# LCR_1.net
KiCad netlist of a schematic drawn in Altium Designer
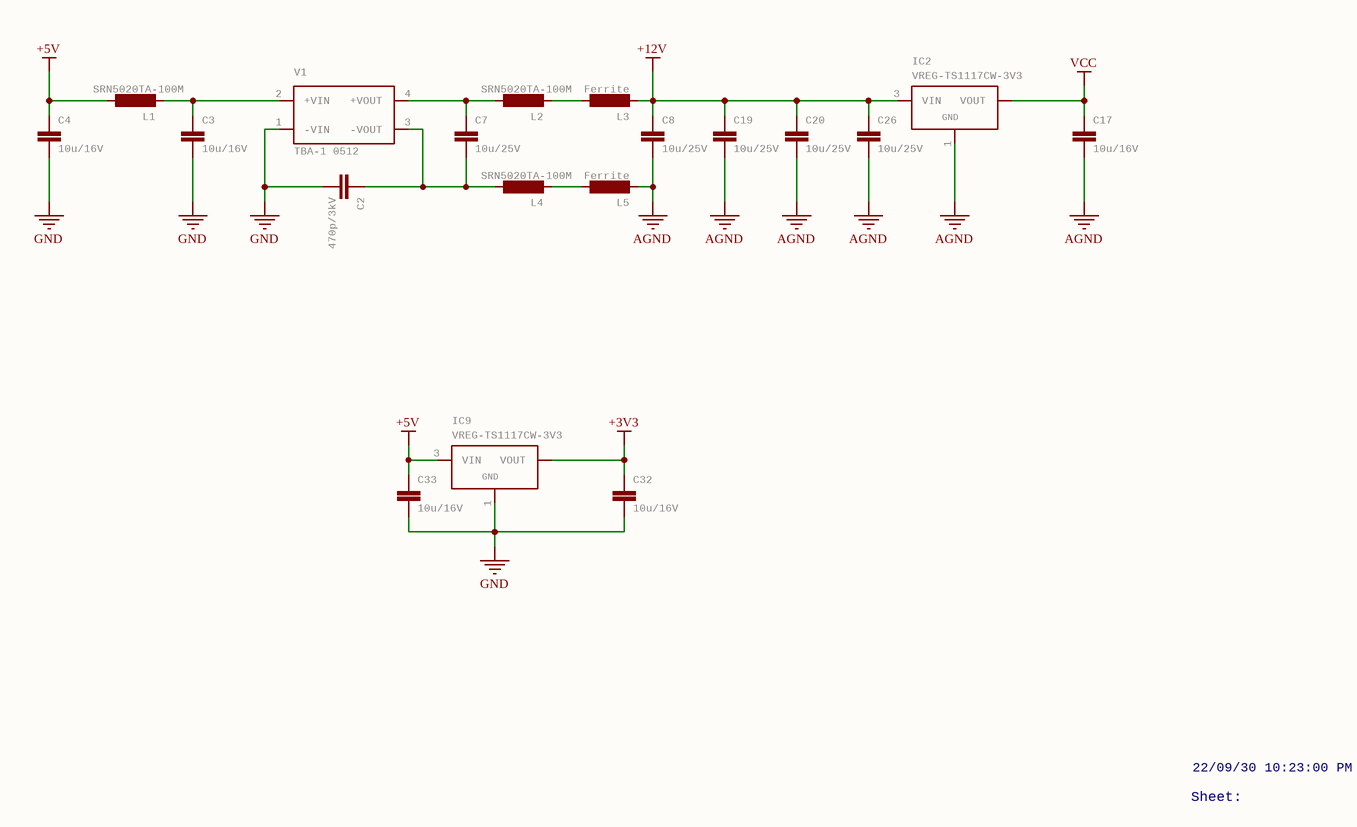
[diagram p0: LCR_1.SchDoc]

(export (version "E")
  (design (tool "Eeschema 10.0.6"))
  (components
    (comp (ref "C2")
      (value "470p/3kV")
      (footprint "C1812")
      (description "CAPACITOR, European symbol")
      (libsource (lib "resistor") (part "C-EUC1812"))
    )
    (comp (ref "C3")
      (value "10u/16V")
      (footprint "C1206K")
      (description "CAPACITOR, European symbol")
      (libsource (lib "rcl") (part "C-EUC1206K"))
    )
    (comp (ref "C4")
      (value "10u/16V")
      (footprint "C1206K")
      (description "CAPACITOR, European symbol")
      (libsource (lib "rcl") (part "C-EUC1206K"))
    )
    (comp (ref "C7")
      (value "10u/25V")
      (footprint "C1206K")
      (description "CAPACITOR, European symbol")
      (libsource (lib "rcl") (part "C-EUC1206K"))
    )
    (comp (ref "C8")
      (value "10u/25V")
      (footprint "C1206K")
      (description "CAPACITOR, European symbol")
      (libsource (lib "rcl") (part "C-EUC1206K"))
    )
    (comp (ref "C17")
      (value "10u/16V")
      (footprint "C1206K")
      (description "CAPACITOR, European symbol")
      (libsource (lib "rcl") (part "C-EUC1206K"))
    )
    (comp (ref "C19")
      (value "10u/25V")
      (footprint "C1206K")
      (description "CAPACITOR, European symbol")
      (libsource (lib "rcl") (part "C-EUC1206K"))
    )
    (comp (ref "C20")
      (value "10u/25V")
      (footprint "C1206K")
      (description "CAPACITOR, European symbol")
      (libsource (lib "rcl") (part "C-EUC1206K"))
    )
    (comp (ref "C26")
      (value "10u/25V")
      (footprint "C1206K")
      (description "CAPACITOR, European symbol")
      (libsource (lib "rcl") (part "C-EUC1206K"))
    )
    (comp (ref "C32")
      (value "10u/16V")
      (footprint "C1206K")
      (description "CAPACITOR, European symbol")
      (libsource (lib "rcl") (part "C-EUC1206K"))
    )
    (comp (ref "C33")
      (value "10u/16V")
      (footprint "C1206K")
      (description "CAPACITOR, European symbol")
      (libsource (lib "rcl") (part "C-EUC1206K"))
    )
    (comp (ref "IC2")
      (value "VREG-TS1117CW-3V3")
      (footprint "SOT223")
      (fields (field (name "GND") "GND"))
      (libsource (lib "we-power-mod") (part "VREG-TS1117CW-3V3"))
    )
    (comp (ref "IC9")
      (value "VREG-TS1117CW-3V3")
      (footprint "SOT223")
      (fields (field (name "GND") "GND"))
      (libsource (lib "we-power-mod") (part "VREG-TS1117CW-3V3"))
    )
    (comp (ref "L1")
      (value "SRN5020TA-100M")
      (footprint "SRN5040")
      (libsource (lib "custom-ic") (part "SRN5040"))
    )
    (comp (ref "L2")
      (value "SRN5020TA-100M")
      (footprint "SRN5040")
      (libsource (lib "custom-ic") (part "SRN5040"))
    )
    (comp (ref "L3") (value "Ferrite") (footprint "R0603") (libsource (lib "rf") (part "INDUCTOR0603")))
    (comp (ref "L4")
      (value "SRN5020TA-100M")
      (footprint "SRN5040")
      (libsource (lib "custom-ic") (part "SRN5040"))
    )
    (comp (ref "L5") (value "Ferrite") (footprint "R0603") (libsource (lib "rf") (part "INDUCTOR0603")))
    (comp (ref "V1")
      (value "TBA-1 0512")
      (footprint "TME")
      (description "DC/DC Converter TME Series 1 Watt    Source: www.tracopower.com .. tme.pdf")
      (fields (field (name "MF") "MF") (field (name "MPN") "TME 0505S"))
      (libsource (lib "traco-electronic") (part "TME?*05"))
    )
  )
  (nets
    (net (code "1") (name "+3V3") (class "Default")
      (node (ref "C32") (pin "1") (pinfunction "1_1") (pintype "passive"))
      (node (ref "IC9") (pin "2_4") (pinfunction "VOUT_2_4") (pintype "power_in"))
    )
    (net (code "2") (name "+5V") (class "Default")
      (node (ref "C33") (pin "1") (pinfunction "1_1") (pintype "passive"))
      (node (ref "C4") (pin "1") (pinfunction "1_1") (pintype "passive"))
      (node (ref "IC9") (pin "3") (pinfunction "VIN_3") (pintype "power_in"))
      (node (ref "L1") (pin "P$1") (pinfunction "1_P$1") (pintype "passive"))
    )
    (net (code "3") (name "+12V") (class "Default")
      (node (ref "C19") (pin "1") (pinfunction "1_1") (pintype "passive"))
      (node (ref "C20") (pin "1") (pinfunction "1_1") (pintype "passive"))
      (node (ref "C26") (pin "1") (pinfunction "1_1") (pintype "passive"))
      (node (ref "C8") (pin "1") (pinfunction "1_1") (pintype "passive"))
      (node (ref "IC2") (pin "3") (pinfunction "VIN_3") (pintype "power_in"))
      (node (ref "L3") (pin "2") (pinfunction "2_2") (pintype "passive"))
    )
    (net (code "4") (name "AGND") (class "Default")
      (node (ref "C17") (pin "2") (pinfunction "2_2") (pintype "passive"))
      (node (ref "C19") (pin "2") (pinfunction "2_2") (pintype "passive"))
      (node (ref "C20") (pin "2") (pinfunction "2_2") (pintype "passive"))
      (node (ref "C26") (pin "2") (pinfunction "2_2") (pintype "passive"))
      (node (ref "C8") (pin "2") (pinfunction "2_2") (pintype "passive"))
      (node (ref "IC2") (pin "1") (pinfunction "GND_1") (pintype "power_in"))
      (node (ref "L5") (pin "2") (pinfunction "2_2") (pintype "passive"))
    )
    (net (code "5") (name "GND") (class "Default")
      (node (ref "C2") (pin "2") (pinfunction "2_2") (pintype "passive"))
      (node (ref "C3") (pin "2") (pinfunction "2_2") (pintype "passive"))
      (node (ref "C32") (pin "2") (pinfunction "2_2") (pintype "passive"))
      (node (ref "C33") (pin "2") (pinfunction "2_2") (pintype "passive"))
      (node (ref "C4") (pin "2") (pinfunction "2_2") (pintype "passive"))
      (node (ref "IC9") (pin "1") (pinfunction "GND_1") (pintype "power_in"))
      (node (ref "V1") (pin "1") (pinfunction "-VIN_1") (pintype "passive"))
    )
    (net (code "6") (name "Net-(L1-2)") (class "Default")
      (node (ref "C3") (pin "1") (pinfunction "1_1") (pintype "passive"))
      (node (ref "L1") (pin "P$2") (pinfunction "2_P$2") (pintype "passive"))
      (node (ref "V1") (pin "2") (pinfunction "+VIN_2") (pintype "passive"))
    )
    (net (code "7") (name "Net-(L2-1)") (class "Default")
      (node (ref "C7") (pin "1") (pinfunction "1_1") (pintype "passive"))
      (node (ref "L2") (pin "P$1") (pinfunction "1_P$1") (pintype "passive"))
      (node (ref "V1") (pin "4") (pinfunction "+VOUT_4") (pintype "passive"))
    )
    (net (code "8") (name "Net-(L2-2)") (class "Default")
      (node (ref "L2") (pin "P$2") (pinfunction "2_P$2") (pintype "passive"))
      (node (ref "L3") (pin "1") (pinfunction "1_1") (pintype "passive"))
    )
    (net (code "9") (name "Net-(L4-1)") (class "Default")
      (node (ref "C2") (pin "1") (pinfunction "1_1") (pintype "passive"))
      (node (ref "C7") (pin "2") (pinfunction "2_2") (pintype "passive"))
      (node (ref "L4") (pin "P$1") (pinfunction "1_P$1") (pintype "passive"))
      (node (ref "V1") (pin "3") (pinfunction "-VOUT_3") (pintype "passive"))
    )
    (net (code "10") (name "Net-(L4-2)") (class "Default")
      (node (ref "L4") (pin "P$2") (pinfunction "2_P$2") (pintype "passive"))
      (node (ref "L5") (pin "1") (pinfunction "1_1") (pintype "passive"))
    )
    (net (code "11") (name "VCC") (class "Default")
      (node (ref "C17") (pin "1") (pinfunction "1_1") (pintype "passive"))
      (node (ref "IC2") (pin "2_4") (pinfunction "VOUT_2_4") (pintype "power_in"))
    )
  )
)
